# Sheet4.net
KiCad netlist of a schematic drawn in Altium Designer
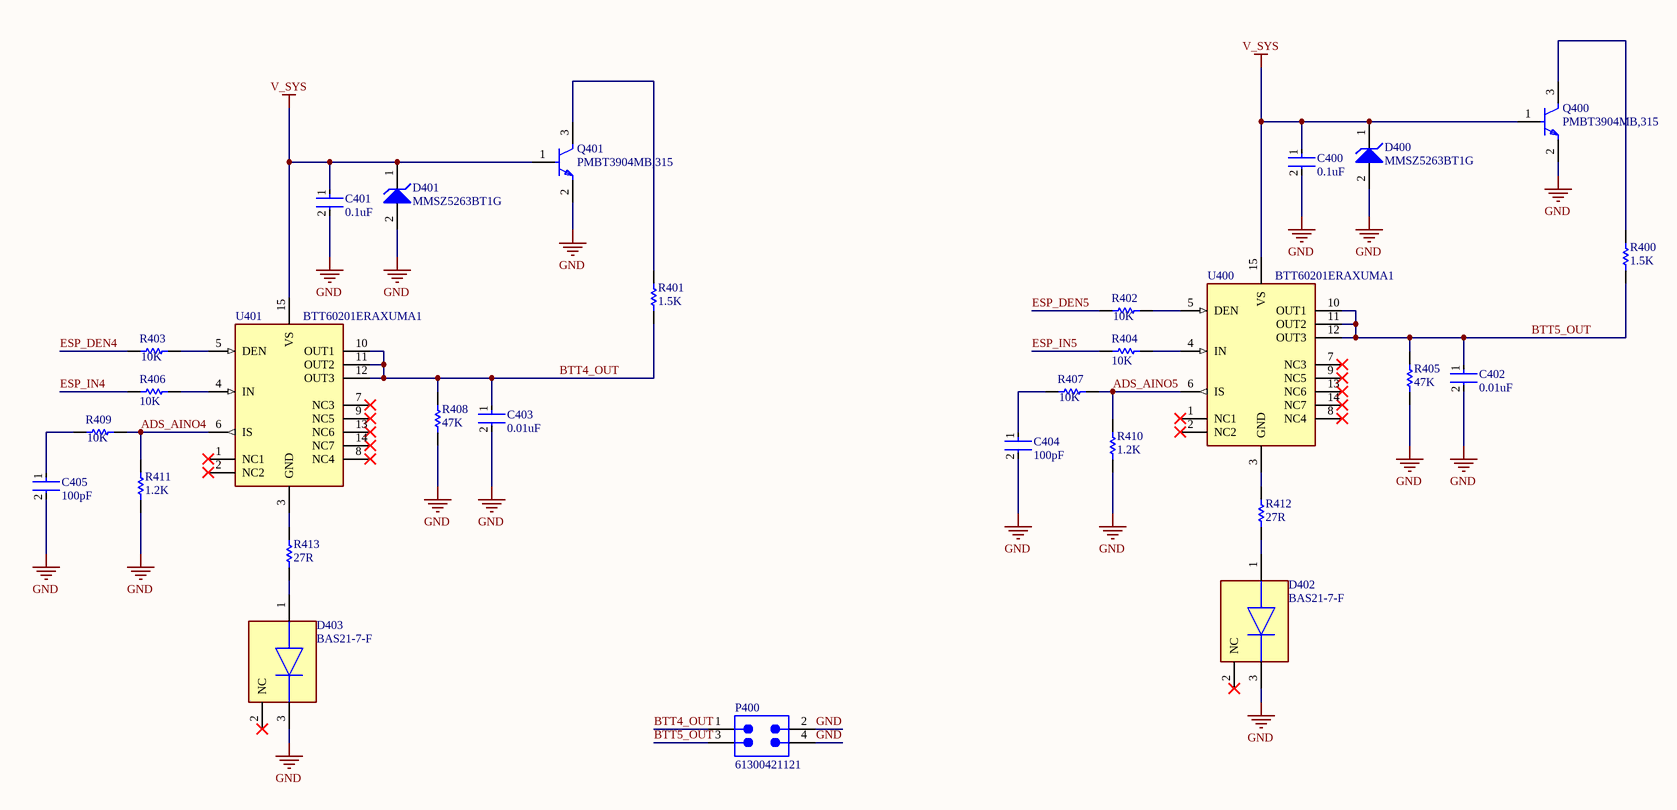
[diagram p0: Sheet4.SchDoc]

(export (version "E")
  (design (tool "Eeschema 10.0.6"))
  (components
    (comp (ref "C400")
      (value "0.1uF")
      (footprint "FP-GRM155-0_05-IPC_B")
      (description "Chip Multilayer Ceramic Capacitors for General Purpose, 0402, 0.10uF, X7R, 15%, 10%, 50V")
      (fields (field (name "VOLTAGE") "50V") (field (name "TOLERANCE") "10%"))
      (libsource (lib "Altium Content Vault") (part "02cd4be3c70576c341d710602a673aa"))
    )
    (comp (ref "C401")
      (value "0.1uF")
      (footprint "FP-GRM155-0_05-IPC_B")
      (description "Chip Multilayer Ceramic Capacitors for General Purpose, 0402, 0.10uF, X7R, 15%, 10%, 50V")
      (fields (field (name "VOLTAGE") "50V") (field (name "TOLERANCE") "10%"))
      (libsource (lib "Altium Content Vault") (part "02cd4be3c70576c341d710602a673aa"))
    )
    (comp (ref "C402")
      (value "0.01uF")
      (footprint "FP-GRM155-0_05-IPC_C")
      (description "Chip Multilayer Ceramic Capacitors for General Purpose, 0402, 10000pF, X7R, 15%, 10%, 50V")
      (fields (field (name "TOLERANCE") "10%") (field (name "VOLTAGE") "25V"))
      (libsource (lib "Altium Content Vault") (part "02cd4be3c70576c341d710602a673aa"))
    )
    (comp (ref "C403")
      (value "0.01uF")
      (footprint "FP-GRM155-0_05-IPC_C")
      (description "Chip Multilayer Ceramic Capacitors for General Purpose, 0402, 10000pF, X7R, 15%, 10%, 50V")
      (fields (field (name "TOLERANCE") "10%") (field (name "VOLTAGE") "25V"))
      (libsource (lib "Altium Content Vault") (part "02cd4be3c70576c341d710602a673aa"))
    )
    (comp (ref "C404")
      (value "100pF")
      (footprint "FP-C0402-BB-MFG")
      (description "CAP CER 100PF 50V C0G/NP0 0402")
      (fields (field (name "MANUFACTURER") "Kemet") (field (name "TOLERANCE") "0.05"))
      (libsource (lib "Altium Content Vault") (part "b4654b650e69147ec39a6b967a45e02"))
    )
    (comp (ref "C405")
      (value "100pF")
      (footprint "FP-C0402-BB-MFG")
      (description "CAP CER 100PF 50V C0G/NP0 0402")
      (fields (field (name "MANUFACTURER") "Kemet") (field (name "TOLERANCE") "0.05"))
      (libsource (lib "Altium Content Vault") (part "b4654b650e69147ec39a6b967a45e02"))
    )
    (comp (ref "D400")
      (value "MMSZ5263BT1G")
      (footprint "ONSC-SOD-123-2-425-04_V")
      (description "Zener Voltage Regulator, 500 mW, 2-Pin SOD-123, Pb-Free, Tape and Reel")
      (fields (field (name "MANUFACTURER") "On Semiconductor"))
      (libsource (lib "Altium Content Vault") (part "ONSC-K1A2-2"))
    )
    (comp (ref "D401")
      (value "MMSZ5263BT1G")
      (footprint "ONSC-SOD-123-2-425-04_V")
      (description "Zener Voltage Regulator, 500 mW, 2-Pin SOD-123, Pb-Free, Tape and Reel")
      (fields (field (name "MANUFACTURER") "On Semiconductor"))
      (libsource (lib "Altium Content Vault") (part "ONSC-K1A2-2"))
    )
    (comp (ref "D402")
      (value "BAS21-7-F")
      (footprint "FP-SOT23-MFG")
      (description "DIODE GEN PURP 200V 200MA SOT23")
      (fields
        (field (name "OCTOPART") "https://octopart.com/bas21-7-f-diodes+inc.-325943")
        (field (name "MANUFACTURER") "Diodes Inc.")
      )
      (libsource (lib "Altium Content Vault") (part "4e36664258fec53a771a927e3978fea"))
    )
    (comp (ref "D403")
      (value "BAS21-7-F")
      (footprint "FP-SOT23-MFG")
      (description "DIODE GEN PURP 200V 200MA SOT23")
      (fields
        (field (name "OCTOPART") "https://octopart.com/bas21-7-f-diodes+inc.-325943")
        (field (name "MANUFACTURER") "Diodes Inc.")
      )
      (libsource (lib "Altium Content Vault") (part "4e36664258fec53a771a927e3978fea"))
    )
    (comp (ref "P400")
      (value "61300421121")
      (footprint "61300421121")
      (description "THT Vertical Pin Header WR-PHD, Pitch 2.54 mm, Dual Row, 4 pins")
      (libsource (lib "Altium Content Vault") (part "Header_Male_2R_04P"))
    )
    (comp (ref "Q400")
      (value "PMBT3904MB,315")
      (footprint "FP-SOT883B-MFG")
      (description "TRANS NPN 40V 0.2A 3DFN")
      (libsource (lib "Altium Content Vault") (part "b44e953556f554d0102664c7d152cb4"))
    )
    (comp (ref "Q401")
      (value "PMBT3904MB,315")
      (footprint "FP-SOT883B-MFG")
      (description "TRANS NPN 40V 0.2A 3DFN")
      (libsource (lib "Altium Content Vault") (part "b44e953556f554d0102664c7d152cb4"))
    )
    (comp (ref "R400")
      (value "1.5K")
      (footprint "RESC1005X40X25ML05T10")
      (fields (field (name "MANUFACTURER") "Yageo / Phycomp") (field (name "PART NUMBER") "RC0402FR-071K5L"))
      (libsource (lib "Altium Content Vault") (part "RES"))
    )
    (comp (ref "R401")
      (value "1.5K")
      (footprint "RESC1005X40X25ML05T10")
      (fields (field (name "MANUFACTURER") "Yageo / Phycomp") (field (name "PART NUMBER") "RC0402FR-071K5L"))
      (libsource (lib "Altium Content Vault") (part "RES"))
    )
    (comp (ref "R402")
      (value "10K")
      (footprint "RESC1005X40X25LL05T10")
      (fields (field (name "PART NUMBER") "RC0402FR-0710KL") (field (name "MANUFACTURER") "Yageo / Phycomp"))
      (libsource (lib "Altium Content Vault") (part "RES"))
    )
    (comp (ref "R403")
      (value "10K")
      (footprint "RESC1005X40X25LL05T10")
      (fields (field (name "PART NUMBER") "RC0402FR-0710KL") (field (name "MANUFACTURER") "Yageo / Phycomp"))
      (libsource (lib "Altium Content Vault") (part "RES"))
    )
    (comp (ref "R404")
      (value "10K")
      (footprint "RESC1005X40X25LL05T10")
      (fields (field (name "PART NUMBER") "RC0402FR-0710KL") (field (name "MANUFACTURER") "Yageo / Phycomp"))
      (libsource (lib "Altium Content Vault") (part "RES"))
    )
    (comp (ref "R405")
      (value "47K")
      (footprint "RESC1005X40X25ML05T10")
      (fields (field (name "PART NUMBER") "RC0402FR-0747KL") (field (name "MANUFACTURER") "Yageo / Phycomp"))
      (libsource (lib "Altium Content Vault") (part "RES"))
    )
    (comp (ref "R406")
      (value "10K")
      (footprint "RESC1005X40X25LL05T10")
      (fields (field (name "PART NUMBER") "RC0402FR-0710KL") (field (name "MANUFACTURER") "Yageo / Phycomp"))
      (libsource (lib "Altium Content Vault") (part "RES"))
    )
    (comp (ref "R407")
      (value "10K")
      (footprint "RESC1005X40X25LL05T10")
      (fields (field (name "PART NUMBER") "RC0402FR-0710KL") (field (name "MANUFACTURER") "Yageo / Phycomp"))
      (libsource (lib "Altium Content Vault") (part "RES"))
    )
    (comp (ref "R408")
      (value "47K")
      (footprint "RESC1005X40X25ML05T10")
      (fields (field (name "PART NUMBER") "RC0402FR-0747KL") (field (name "MANUFACTURER") "Yageo / Phycomp"))
      (libsource (lib "Altium Content Vault") (part "RES"))
    )
    (comp (ref "R409")
      (value "10K")
      (footprint "RESC1005X40X25LL05T10")
      (fields (field (name "PART NUMBER") "RC0402FR-0710KL") (field (name "MANUFACTURER") "Yageo / Phycomp"))
      (libsource (lib "Altium Content Vault") (part "RES"))
    )
    (comp (ref "R410")
      (value "1.2K")
      (footprint "RESC1005X40X25ML05T10")
      (fields (field (name "PART NUMBER") "RC0402FR-071K2L") (field (name "MANUFACTURER") "Yageo / Phycomp"))
      (libsource (lib "Altium Content Vault") (part "RES"))
    )
    (comp (ref "R411")
      (value "1.2K")
      (footprint "RESC1005X40X25ML05T10")
      (fields (field (name "PART NUMBER") "RC0402FR-071K2L") (field (name "MANUFACTURER") "Yageo / Phycomp"))
      (libsource (lib "Altium Content Vault") (part "RES"))
    )
    (comp (ref "R412")
      (value "27R")
      (footprint "RESC1005X40X25LL05T10")
      (fields (field (name "PART NUMBER") "RC0402FR-0727RL") (field (name "MANUFACTURER") "Yageo / Phycomp"))
      (libsource (lib "Altium Content Vault") (part "RES"))
    )
    (comp (ref "R413")
      (value "27R")
      (footprint "RESC1005X40X25LL05T10")
      (fields (field (name "PART NUMBER") "RC0402FR-0727RL") (field (name "MANUFACTURER") "Yageo / Phycomp"))
      (libsource (lib "Altium Content Vault") (part "RES"))
    )
    (comp (ref "U400")
      (value "BTT60201ERAXUMA1")
      (footprint "BTT60201ERAXUMA1")
      (description "Power Switch ICs – Power Distribution; INFINEON; BTT60201ERAXUMA1; 1; 7 A")
      (fields (field (name "MANUFACTURER") "Infineon"))
      (libsource (lib "HW_SSB") (part "BTT60201ERAXUMA1"))
    )
    (comp (ref "U401")
      (value "BTT60201ERAXUMA1")
      (footprint "BTT60201ERAXUMA1")
      (description "Power Switch ICs – Power Distribution; INFINEON; BTT60201ERAXUMA1; 1; 7 A")
      (fields (field (name "MANUFACTURER") "Infineon"))
      (libsource (lib "HW_SSB") (part "BTT60201ERAXUMA1"))
    )
  )
  (nets
    (net (code "1") (name "/ADS_AINO4") (class "Default")
      (node (ref "R409") (pin "2") (pinfunction "2_2") (pintype "passive"))
      (node (ref "R411") (pin "2") (pinfunction "2_2") (pintype "passive"))
      (node (ref "U401") (pin "6") (pinfunction "IS_6") (pintype "output"))
    )
    (net (code "2") (name "/ADS_AINO5") (class "Default")
      (node (ref "R407") (pin "2") (pinfunction "2_2") (pintype "passive"))
      (node (ref "R410") (pin "2") (pinfunction "2_2") (pintype "passive"))
      (node (ref "U400") (pin "6") (pinfunction "IS_6") (pintype "output"))
    )
    (net (code "3") (name "/BTT4_OUT") (class "Default")
      (node (ref "C403") (pin "1") (pinfunction "1_1") (pintype "passive"))
      (node (ref "P400") (pin "1") (pinfunction "1_1") (pintype "passive"))
      (node (ref "R401") (pin "1") (pinfunction "1_1") (pintype "passive"))
      (node (ref "R408") (pin "2") (pinfunction "2_2") (pintype "passive"))
      (node (ref "U401") (pin "10") (pinfunction "OUT1_10") (pintype "passive"))
      (node (ref "U401") (pin "11") (pinfunction "OUT2_11") (pintype "passive"))
      (node (ref "U401") (pin "12") (pinfunction "OUT3_12") (pintype "passive"))
    )
    (net (code "4") (name "/BTT5_OUT") (class "Default")
      (node (ref "C402") (pin "1") (pinfunction "1_1") (pintype "passive"))
      (node (ref "P400") (pin "3") (pinfunction "3_3") (pintype "passive"))
      (node (ref "R400") (pin "1") (pinfunction "1_1") (pintype "passive"))
      (node (ref "R405") (pin "2") (pinfunction "2_2") (pintype "passive"))
      (node (ref "U400") (pin "10") (pinfunction "OUT1_10") (pintype "passive"))
      (node (ref "U400") (pin "11") (pinfunction "OUT2_11") (pintype "passive"))
      (node (ref "U400") (pin "12") (pinfunction "OUT3_12") (pintype "passive"))
    )
    (net (code "5") (name "/ESP_DEN4") (class "Default")
      (node (ref "R403") (pin "1") (pinfunction "1_1") (pintype "passive"))
    )
    (net (code "6") (name "/ESP_DEN5") (class "Default")
      (node (ref "R402") (pin "1") (pinfunction "1_1") (pintype "passive"))
    )
    (net (code "7") (name "/ESP_IN4") (class "Default")
      (node (ref "R406") (pin "1") (pinfunction "1_1") (pintype "passive"))
    )
    (net (code "8") (name "/ESP_IN5") (class "Default")
      (node (ref "R404") (pin "1") (pinfunction "1_1") (pintype "passive"))
    )
    (net (code "9") (name "GND") (class "Default")
      (node (ref "C400") (pin "2") (pinfunction "2_2") (pintype "passive"))
      (node (ref "C401") (pin "2") (pinfunction "2_2") (pintype "passive"))
      (node (ref "C402") (pin "2") (pinfunction "2_2") (pintype "passive"))
      (node (ref "C403") (pin "2") (pinfunction "2_2") (pintype "passive"))
      (node (ref "C404") (pin "2") (pinfunction "2_2") (pintype "passive"))
      (node (ref "C405") (pin "2") (pinfunction "2_2") (pintype "passive"))
      (node (ref "D400") (pin "2") (pinfunction "A_2") (pintype "passive"))
      (node (ref "D401") (pin "2") (pinfunction "A_2") (pintype "passive"))
      (node (ref "D402") (pin "3") (pinfunction "C_3") (pintype "passive"))
      (node (ref "D403") (pin "3") (pinfunction "C_3") (pintype "passive"))
      (node (ref "P400") (pin "2") (pinfunction "2_2") (pintype "passive"))
      (node (ref "P400") (pin "4") (pinfunction "4_4") (pintype "passive"))
      (node (ref "Q400") (pin "2") (pinfunction "E_2") (pintype "passive"))
      (node (ref "Q401") (pin "2") (pinfunction "E_2") (pintype "passive"))
      (node (ref "R405") (pin "1") (pinfunction "1_1") (pintype "passive"))
      (node (ref "R408") (pin "1") (pinfunction "1_1") (pintype "passive"))
      (node (ref "R410") (pin "1") (pinfunction "1_1") (pintype "passive"))
      (node (ref "R411") (pin "1") (pinfunction "1_1") (pintype "passive"))
    )
    (net (code "10") (name "Net-(C404-Pad1)") (class "Default")
      (node (ref "C404") (pin "1") (pinfunction "1_1") (pintype "passive"))
      (node (ref "R407") (pin "1") (pinfunction "1_1") (pintype "passive"))
    )
    (net (code "11") (name "Net-(C405-Pad1)") (class "Default")
      (node (ref "C405") (pin "1") (pinfunction "1_1") (pintype "passive"))
      (node (ref "R409") (pin "1") (pinfunction "1_1") (pintype "passive"))
    )
    (net (code "12") (name "Net-(D402-A)") (class "Default")
      (node (ref "D402") (pin "1") (pinfunction "A_1") (pintype "passive"))
      (node (ref "R412") (pin "1") (pinfunction "1_1") (pintype "passive"))
    )
    (net (code "13") (name "Net-(D403-A)") (class "Default")
      (node (ref "D403") (pin "1") (pinfunction "A_1") (pintype "passive"))
      (node (ref "R413") (pin "1") (pinfunction "1_1") (pintype "passive"))
    )
    (net (code "14") (name "Net-(Q400-C)") (class "Default")
      (node (ref "Q400") (pin "3") (pinfunction "C_3") (pintype "passive"))
      (node (ref "R400") (pin "2") (pinfunction "2_2") (pintype "passive"))
    )
    (net (code "15") (name "Net-(Q401-C)") (class "Default")
      (node (ref "Q401") (pin "3") (pinfunction "C_3") (pintype "passive"))
      (node (ref "R401") (pin "2") (pinfunction "2_2") (pintype "passive"))
    )
    (net (code "16") (name "Net-(U400-DEN)") (class "Default")
      (node (ref "R402") (pin "2") (pinfunction "2_2") (pintype "passive"))
      (node (ref "U400") (pin "5") (pinfunction "DEN_5") (pintype "input"))
    )
    (net (code "17") (name "Net-(U400-GND)") (class "Default")
      (node (ref "R412") (pin "2") (pinfunction "2_2") (pintype "passive"))
      (node (ref "U400") (pin "3") (pinfunction "GND_3") (pintype "power_in"))
    )
    (net (code "18") (name "Net-(U400-IN)") (class "Default")
      (node (ref "R404") (pin "2") (pinfunction "2_2") (pintype "passive"))
      (node (ref "U400") (pin "4") (pinfunction "IN_4") (pintype "input"))
    )
    (net (code "19") (name "Net-(U401-DEN)") (class "Default")
      (node (ref "R403") (pin "2") (pinfunction "2_2") (pintype "passive"))
      (node (ref "U401") (pin "5") (pinfunction "DEN_5") (pintype "input"))
    )
    (net (code "20") (name "Net-(U401-GND)") (class "Default")
      (node (ref "R413") (pin "2") (pinfunction "2_2") (pintype "passive"))
      (node (ref "U401") (pin "3") (pinfunction "GND_3") (pintype "power_in"))
    )
    (net (code "21") (name "Net-(U401-IN)") (class "Default")
      (node (ref "R406") (pin "2") (pinfunction "2_2") (pintype "passive"))
      (node (ref "U401") (pin "4") (pinfunction "IN_4") (pintype "input"))
    )
    (net (code "22") (name "V_SYS") (class "Default")
      (node (ref "C400") (pin "1") (pinfunction "1_1") (pintype "passive"))
      (node (ref "C401") (pin "1") (pinfunction "1_1") (pintype "passive"))
      (node (ref "D400") (pin "1") (pinfunction "K_1") (pintype "passive"))
      (node (ref "D401") (pin "1") (pinfunction "K_1") (pintype "passive"))
      (node (ref "Q400") (pin "1") (pinfunction "B_1") (pintype "passive"))
      (node (ref "Q401") (pin "1") (pinfunction "B_1") (pintype "passive"))
      (node (ref "U400") (pin "15") (pinfunction "VS_15") (pintype "power_in"))
      (node (ref "U401") (pin "15") (pinfunction "VS_15") (pintype "power_in"))
    )
    (net (code "23") (name "unconnected-(D402-NC-Pad2)") (class "Default")
      (node (ref "D402") (pin "2") (pinfunction "NC_2") (pintype "passive+no_connect"))
    )
    (net (code "24") (name "unconnected-(D403-NC-Pad2)") (class "Default")
      (node (ref "D403") (pin "2") (pinfunction "NC_2") (pintype "passive+no_connect"))
    )
    (net (code "25") (name "unconnected-(U400-NC1-Pad1)") (class "Default")
      (node (ref "U400") (pin "1") (pinfunction "NC1_1") (pintype "passive+no_connect"))
    )
    (net (code "26") (name "unconnected-(U400-NC2-Pad2)") (class "Default")
      (node (ref "U400") (pin "2") (pinfunction "NC2_2") (pintype "passive+no_connect"))
    )
    (net (code "27") (name "unconnected-(U400-NC3-Pad7)") (class "Default")
      (node (ref "U400") (pin "7") (pinfunction "NC3_7") (pintype "passive+no_connect"))
    )
    (net (code "28") (name "unconnected-(U400-NC4-Pad8)") (class "Default")
      (node (ref "U400") (pin "8") (pinfunction "NC4_8") (pintype "passive+no_connect"))
    )
    (net (code "29") (name "unconnected-(U400-NC5-Pad9)") (class "Default")
      (node (ref "U400") (pin "9") (pinfunction "NC5_9") (pintype "passive+no_connect"))
    )
    (net (code "30") (name "unconnected-(U400-NC6-Pad13)") (class "Default")
      (node (ref "U400") (pin "13") (pinfunction "NC6_13") (pintype "passive+no_connect"))
    )
    (net (code "31") (name "unconnected-(U400-NC7-Pad14)") (class "Default")
      (node (ref "U400") (pin "14") (pinfunction "NC7_14") (pintype "passive+no_connect"))
    )
    (net (code "32") (name "unconnected-(U401-NC1-Pad1)") (class "Default")
      (node (ref "U401") (pin "1") (pinfunction "NC1_1") (pintype "passive+no_connect"))
    )
    (net (code "33") (name "unconnected-(U401-NC2-Pad2)") (class "Default")
      (node (ref "U401") (pin "2") (pinfunction "NC2_2") (pintype "passive+no_connect"))
    )
    (net (code "34") (name "unconnected-(U401-NC3-Pad7)") (class "Default")
      (node (ref "U401") (pin "7") (pinfunction "NC3_7") (pintype "passive+no_connect"))
    )
    (net (code "35") (name "unconnected-(U401-NC4-Pad8)") (class "Default")
      (node (ref "U401") (pin "8") (pinfunction "NC4_8") (pintype "passive+no_connect"))
    )
    (net (code "36") (name "unconnected-(U401-NC5-Pad9)") (class "Default")
      (node (ref "U401") (pin "9") (pinfunction "NC5_9") (pintype "passive+no_connect"))
    )
    (net (code "37") (name "unconnected-(U401-NC6-Pad13)") (class "Default")
      (node (ref "U401") (pin "13") (pinfunction "NC6_13") (pintype "passive+no_connect"))
    )
    (net (code "38") (name "unconnected-(U401-NC7-Pad14)") (class "Default")
      (node (ref "U401") (pin "14") (pinfunction "NC7_14") (pintype "passive+no_connect"))
    )
  )
)
